# 22-RGMII_ETHERNET_PHY_-_MCU.net
KiCad netlist of a schematic drawn in Altium Designer
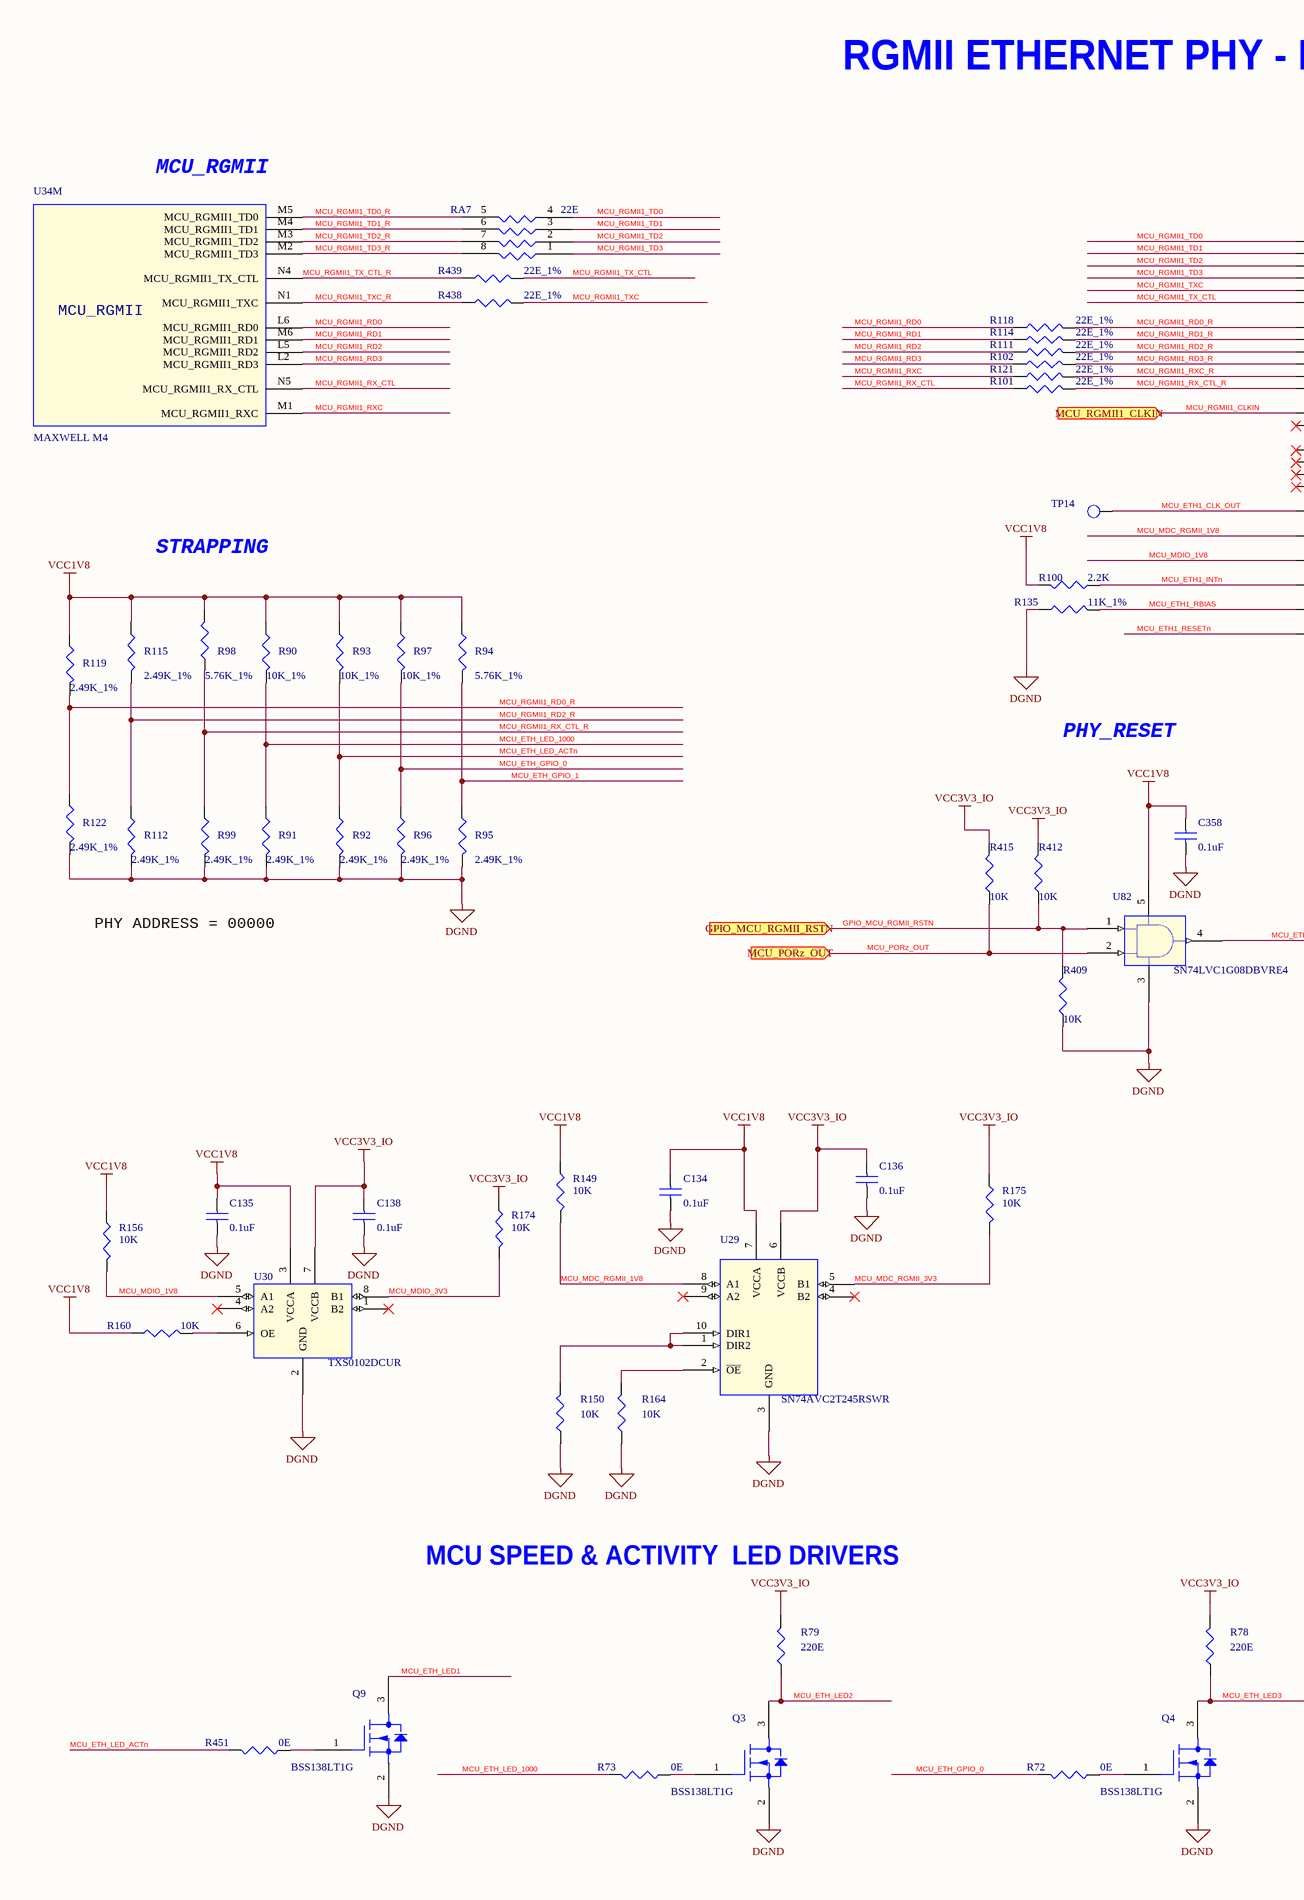
[diagram p0: 22-RGMII ETHERNET PHY - MCU.SchDoc, left]
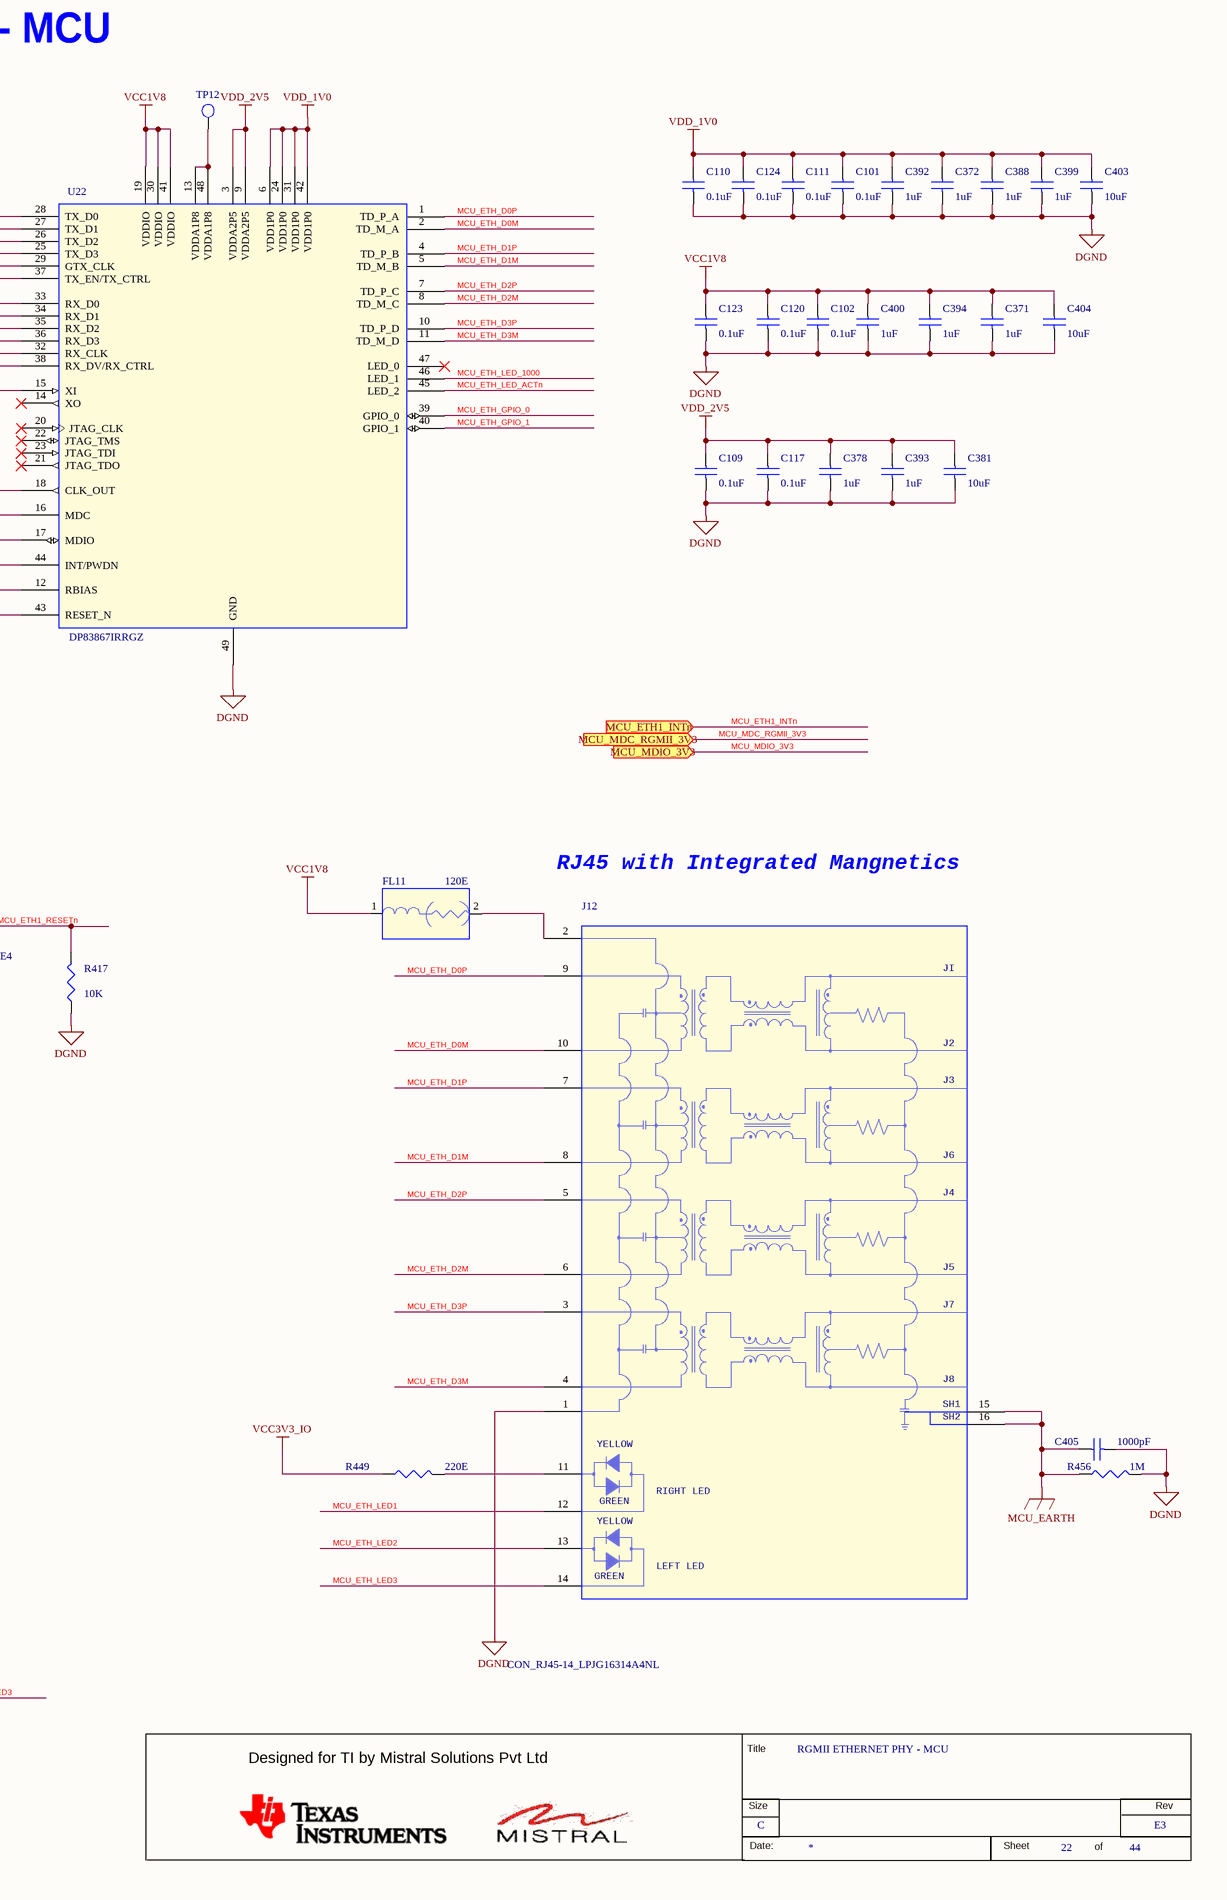
[diagram p1: 22-RGMII ETHERNET PHY - MCU.SchDoc, right]

(export (version "E")
  (design (tool "Eeschema 10.0.6"))
  (components
    (comp (ref "C101")
      (value "0.1uF")
      (footprint "CAP0201_0-5")
      (description "CAP CERAMIC 0.1uF 16V 10% X5R 0201")
      (fields
        (field (name "MISTRAL PART NO") "120009030072-R")
        (field (name "MFR_PART_NUMBER") "GRM033R61C104KE84J")
      )
      (libsource (lib "*") (part "CAP_Dup5"))
    )
    (comp (ref "C102")
      (value "0.1uF")
      (footprint "CAP0201_0-5")
      (description "CAP CERAMIC 0.1uF 16V 10% X5R 0201")
      (fields
        (field (name "MISTRAL PART NO") "120009030072-R")
        (field (name "MFR_PART_NUMBER") "GRM033R61C104KE84J")
      )
      (libsource (lib "*") (part "CAP_Dup5"))
    )
    (comp (ref "C109")
      (value "0.1uF")
      (footprint "CAP0201_0-5")
      (description "CAP CERAMIC 0.1uF 16V 10% X5R 0201")
      (fields (field (name "DISTRIBUTOR_PART_NUMBER") "490-16742-1-ND") (field (name "VOLTAGE") "16V"))
      (libsource (lib "*") (part "CAP_Dup5"))
    )
    (comp (ref "C110")
      (value "0.1uF")
      (footprint "CAP0201_0-5")
      (description "CAP CERAMIC 0.1uF 16V 10% X5R 0201")
      (fields (field (name "DISTRIBUTOR_PART_NUMBER") "490-16742-1-ND") (field (name "VOLTAGE") "16V"))
      (libsource (lib "*") (part "CAP_Dup5"))
    )
    (comp (ref "C111")
      (value "0.1uF")
      (footprint "CAP0201_0-5")
      (description "CAP CERAMIC 0.1uF 16V 10% X5R 0201")
      (fields
        (field (name "MISTRAL PART NO") "120009030072-R")
        (field (name "MFR_PART_NUMBER") "GRM033R61C104KE84J")
      )
      (libsource (lib "*") (part "CAP_Dup5"))
    )
    (comp (ref "C117")
      (value "0.1uF")
      (footprint "CAP0201_0-5")
      (description "CAP CERAMIC 0.1uF 16V 10% X5R 0201")
      (fields
        (field (name "MISTRAL PART NO") "120009030072-R")
        (field (name "MFR_PART_NUMBER") "GRM033R61C104KE84J")
      )
      (libsource (lib "*") (part "CAP_Dup5"))
    )
    (comp (ref "C120")
      (value "0.1uF")
      (footprint "CAP0201_0-5")
      (description "CAP CERAMIC 0.1uF 16V 10% X5R 0201")
      (fields
        (field (name "MISTRAL PART NO") "120009030072-R")
        (field (name "MFR_PART_NUMBER") "GRM033R61C104KE84J")
      )
      (libsource (lib "*") (part "CAP_Dup5"))
    )
    (comp (ref "C123")
      (value "0.1uF")
      (footprint "CAP0201_0-5")
      (description "CAP CERAMIC 0.1uF 16V 10% X5R 0201")
      (fields
        (field (name "MISTRAL PART NO") "120009030072-R")
        (field (name "MFR_PART_NUMBER") "GRM033R61C104KE84J")
      )
      (libsource (lib "*") (part "CAP_Dup5"))
    )
    (comp (ref "C124")
      (value "0.1uF")
      (footprint "CAP0201_0-5")
      (description "CAP CERAMIC 0.1uF 16V 10% X5R 0201")
      (fields (field (name "DISTRIBUTOR_PART_NUMBER") "490-16742-1-ND") (field (name "VOLTAGE") "16V"))
      (libsource (lib "*") (part "CAP_Dup5"))
    )
    (comp (ref "C134")
      (value "0.1uF")
      (footprint "CAP0201_0-5")
      (description "CAP CERAMIC 0.1uF 16V 10% X5R 0201")
      (fields (field (name "DISTRIBUTOR_PART_NUMBER") "490-16742-1-ND") (field (name "VOLTAGE") "16V"))
      (libsource (lib "*") (part "CAP_Dup5"))
    )
    (comp (ref "C135")
      (value "0.1uF")
      (footprint "CAP0201_0-5")
      (description "CAP CERAMIC 0.1uF 16V 10% X5R 0201")
      (fields (field (name "DISTRIBUTOR_PART_NUMBER") "490-16742-1-ND") (field (name "VOLTAGE") "16V"))
      (libsource (lib "*") (part "CAP_Dup5"))
    )
    (comp (ref "C136")
      (value "0.1uF")
      (footprint "CAP0201_0-5")
      (description "CAP CERAMIC 0.1uF 16V 10% X5R 0201")
      (fields (field (name "DISTRIBUTOR_PART_NUMBER") "490-16742-1-ND") (field (name "VOLTAGE") "16V"))
      (libsource (lib "*") (part "CAP_Dup5"))
    )
    (comp (ref "C138")
      (value "0.1uF")
      (footprint "CAP0201_0-5")
      (description "CAP CERAMIC 0.1uF 16V 10% X5R 0201")
      (fields (field (name "DISTRIBUTOR_PART_NUMBER") "490-16742-1-ND") (field (name "VOLTAGE") "16V"))
      (libsource (lib "*") (part "CAP_Dup5"))
    )
    (comp (ref "C358")
      (value "0.1uF")
      (footprint "CAP0201_0-5")
      (description "CAP CERAMIC 0.1uF 16V 10% X5R 0201")
      (fields (field (name "DISTRIBUTOR_PART_NUMBER") "490-16742-1-ND") (field (name "VOLTAGE") "16V"))
      (libsource (lib "*") (part "CAP_Dup5"))
    )
    (comp (ref "C371")
      (value "1uF")
      (footprint "CAP0402_0-75")
      (description "CAP CERAMIC 1uF 16V 20% X5R 0402")
      (fields
        (field (name "MISTRAL PART NO") "120018020006-R")
        (field (name "MFR_PART_NUMBER") "EMK105BJ105MV-F")
      )
      (libsource (lib "*") (part "CAP_Dup5"))
    )
    (comp (ref "C372")
      (value "1uF")
      (footprint "CAP0402_0-75")
      (description "CAP CERAMIC 1uF 16V 20% X5R 0402")
      (fields
        (field (name "MISTRAL PART NO") "120018020006-R")
        (field (name "MFR_PART_NUMBER") "EMK105BJ105MV-F")
      )
      (libsource (lib "*") (part "CAP_Dup5"))
    )
    (comp (ref "C378")
      (value "1uF")
      (footprint "CAP0402_0-75")
      (description "CAP CERAMIC 1uF 16V 20% X5R 0402")
      (fields (field (name "DISTRIBUTOR_PART_NUMBER") "587-5514-1-ND") (field (name "VOLTAGE") "16V"))
      (libsource (lib "*") (part "CAP_Dup5"))
    )
    (comp (ref "C381")
      (value "10uF")
      (footprint "CAP0603_1")
      (description "CAP CERAMIC 10uF 10V 10% X5R 0603")
      (fields (field (name "DISTRIBUTOR_PART_NUMBER") "478-10766-1-ND") (field (name "VOLTAGE") "10V"))
      (libsource (lib "*") (part "CAP_Dup5"))
    )
    (comp (ref "C388")
      (value "1uF")
      (footprint "CAP0402_0-75")
      (description "CAP CERAMIC 1uF 16V 20% X5R 0402")
      (fields (field (name "DISTRIBUTOR_PART_NUMBER") "587-5514-1-ND") (field (name "VOLTAGE") "16V"))
      (libsource (lib "*") (part "CAP_Dup5"))
    )
    (comp (ref "C392")
      (value "1uF")
      (footprint "CAP0402_0-75")
      (description "CAP CERAMIC 1uF 16V 20% X5R 0402")
      (fields (field (name "DISTRIBUTOR_PART_NUMBER") "587-5514-1-ND") (field (name "VOLTAGE") "16V"))
      (libsource (lib "*") (part "CAP_Dup5"))
    )
    (comp (ref "C393")
      (value "1uF")
      (footprint "CAP0402_0-75")
      (description "CAP CERAMIC 1uF 16V 20% X5R 0402")
      (fields (field (name "DISTRIBUTOR_PART_NUMBER") "587-5514-1-ND") (field (name "VOLTAGE") "16V"))
      (libsource (lib "*") (part "CAP_Dup5"))
    )
    (comp (ref "C394")
      (value "1uF")
      (footprint "CAP0402_0-75")
      (description "CAP CERAMIC 1uF 16V 20% X5R 0402")
      (fields
        (field (name "MISTRAL PART NO") "120018020006-R")
        (field (name "MFR_PART_NUMBER") "EMK105BJ105MV-F")
      )
      (libsource (lib "*") (part "CAP_Dup5"))
    )
    (comp (ref "C399")
      (value "1uF")
      (footprint "CAP0402_0-75")
      (description "CAP CERAMIC 1uF 16V 20% X5R 0402")
      (fields
        (field (name "MISTRAL PART NO") "120018020006-R")
        (field (name "MFR_PART_NUMBER") "EMK105BJ105MV-F")
      )
      (libsource (lib "*") (part "CAP_Dup5"))
    )
    (comp (ref "C400")
      (value "1uF")
      (footprint "CAP0402_0-75")
      (description "CAP CERAMIC 1uF 16V 20% X5R 0402")
      (fields
        (field (name "MISTRAL PART NO") "120018020006-R")
        (field (name "MFR_PART_NUMBER") "EMK105BJ105MV-F")
      )
      (libsource (lib "*") (part "CAP_Dup5"))
    )
    (comp (ref "C403")
      (value "10uF")
      (footprint "CAP0603_1")
      (description "CAP CERAMIC 10uF 10V 10% X5R 0603")
      (fields (field (name "DISTRIBUTOR_PART_NUMBER") "478-10766-1-ND") (field (name "VOLTAGE") "10V"))
      (libsource (lib "*") (part "CAP_Dup5"))
    )
    (comp (ref "C404")
      (value "10uF")
      (footprint "CAP0603_1")
      (description "CAP CERAMIC 10uF 10V 10% X5R 0603")
      (fields
        (field (name "MISTRAL PART NO") "120010080001-R")
        (field (name "MFR_PART_NUMBER") "0603ZD106KAT2A")
      )
      (libsource (lib "*") (part "CAP_Dup5"))
    )
    (comp (ref "C405")
      (value "1000pF")
      (footprint "CAP1206")
      (description "CAP CERAMIC 1000pF 2KV 10% X7R 1206")
      (fields
        (field (name "MISTRAL PART NO") "120009030147-R")
        (field (name "MFR_PART_NUMBER") "1206GC102KAT1A")
      )
      (libsource (lib "*") (part "CAP_Dup5"))
    )
    (comp (ref "FL11")
      (value "120E")
      (footprint "EMIFIL_BLM15A_0402_0-6")
      (description "FERRITE CHIP 120E 1.3A 0402")
      (fields
        (field (name "MISTRAL PART NO") "130012030043-R")
        (field (name "MFR_PART_NUMBER") "BLM15PD121SN1")
      )
      (libsource (lib "*") (part "EMIFILTER_IND"))
    )
    (comp (ref "J12")
      (value "CON_RJ45-14_LPJG16314A4NL")
      (footprint "CON_RJ45-14_LPJG16314A4NL_S_R_T_13-6")
      (description "CON RJ-45 FEMALE 14POS RT TH")
      (fields (field (name "DISTRIBUTOR_PART_NUMBER") "NA") (field (name "MFR_PART_NUMBER") "LPJG16314A4NL"))
      (libsource (lib "*") (part "CON_RJ45-14_LPJG16314A4NL"))
    )
    (comp (ref "Q3")
      (value "BSS138LT1G")
      (footprint "SOT23-123")
      (description "IC MOSFET N-CHANNEL 50V, SOT23-3")
      (fields (field (name "MISTRAL PART NO") "142016040001-R") (field (name "TOLERANCE") "NA"))
      (libsource (lib "*") (part "MOSFET_BSS138LT1G"))
    )
    (comp (ref "Q4")
      (value "BSS138LT1G")
      (footprint "SOT23-123")
      (description "IC MOSFET N-CHANNEL 50V, SOT23-3")
      (fields (field (name "MISTRAL PART NO") "142016040001-R") (field (name "TOLERANCE") "NA"))
      (libsource (lib "*") (part "MOSFET_BSS138LT1G"))
    )
    (comp (ref "Q9")
      (value "BSS138LT1G")
      (footprint "SOT23-123")
      (description "IC MOSFET N-CHANNEL 50V, SOT23-3")
      (fields (field (name "MISTRAL PART NO") "142016040001-R") (field (name "TOLERANCE") "NA"))
      (libsource (lib "*") (part "MOSFET_BSS138LT1G"))
    )
    (comp (ref "R72")
      (value "0E")
      (footprint "RES0402_0-5")
      (description "RES 0E 1/16W 0402")
      (fields
        (field (name "MISTRAL PART NO") "110010080019-P")
        (field (name "MFR_PART_NUMBER") "CRCW04020000Z0ED")
      )
      (libsource (lib "*") (part "RESISTOR_Dup4"))
    )
    (comp (ref "R73")
      (value "0E")
      (footprint "RES0402_0-5")
      (description "RES 0E 1/16W 0402")
      (fields
        (field (name "MISTRAL PART NO") "110010080019-P")
        (field (name "MFR_PART_NUMBER") "CRCW04020000Z0ED")
      )
      (libsource (lib "*") (part "RESISTOR_Dup4"))
    )
    (comp (ref "R78")
      (value "220E")
      (footprint "RES0402_0-5")
      (description "RES 220E 1/16W 5% 0402")
      (fields
        (field (name "MISTRAL PART NO") "110009030506-R")
        (field (name "MFR_PART_NUMBER") "ERJ-2GEJ221X")
      )
      (libsource (lib "*") (part "RESISTOR_Dup5"))
    )
    (comp (ref "R79")
      (value "220E")
      (footprint "RES0402_0-5")
      (description "RES 220E 1/16W 5% 0402")
      (fields
        (field (name "MISTRAL PART NO") "110009030506-R")
        (field (name "MFR_PART_NUMBER") "ERJ-2GEJ221X")
      )
      (libsource (lib "*") (part "RESISTOR_Dup5"))
    )
    (comp (ref "R90")
      (value "10K_1%")
      (footprint "RES0402_0-5")
      (description "RES 10K 1/16W 1% 0402")
      (fields (field (name "DISTRIBUTOR_PART_NUMBER") "311-10.0KLRTR-ND") (field (name "VOLTAGE") "NA"))
      (libsource (lib "*") (part "RESISTOR_Dup5"))
    )
    (comp (ref "R91")
      (value "2.49K_1%")
      (footprint "RES0402")
      (description "RES 2.49K 1/16W 1% 0402")
      (fields
        (field (name "MISTRAL PART NO") "110016050020-R")
        (field (name "MFR_PART_NUMBER") "RC0402FR-072K49L")
      )
      (libsource (lib "*") (part "RESISTOR_Dup5"))
    )
    (comp (ref "R92")
      (value "2.49K_1%")
      (footprint "RES0402")
      (description "RES 2.49K 1/16W 1% 0402")
      (fields
        (field (name "MISTRAL PART NO") "110016050020-R")
        (field (name "MFR_PART_NUMBER") "RC0402FR-072K49L")
      )
      (libsource (lib "*") (part "RESISTOR_Dup5"))
    )
    (comp (ref "R93")
      (value "10K_1%")
      (footprint "RES0402_0-5")
      (description "RES 10K 1/16W 1% 0402")
      (fields (field (name "DISTRIBUTOR_PART_NUMBER") "311-10.0KLRTR-ND") (field (name "VOLTAGE") "NA"))
      (libsource (lib "*") (part "RESISTOR_Dup5"))
    )
    (comp (ref "R94")
      (value "5.76K_1%")
      (footprint "RES0402")
      (description "RES 5.76K 1/10W 1% 0402")
      (fields
        (field (name "MISTRAL PART NO") "110009030945-R")
        (field (name "MFR_PART_NUMBER") "ERJ-2RKF5761X")
      )
      (libsource (lib "*") (part "RESISTOR_Dup5"))
    )
    (comp (ref "R95")
      (value "2.49K_1%")
      (footprint "RES0402")
      (description "RES 2.49K 1/16W 1% 0402")
      (fields
        (field (name "MISTRAL PART NO") "110016050020-R")
        (field (name "MFR_PART_NUMBER") "RC0402FR-072K49L")
      )
      (libsource (lib "*") (part "RESISTOR_Dup5"))
    )
    (comp (ref "R96")
      (value "2.49K_1%")
      (footprint "RES0402")
      (description "RES 2.49K 1/16W 1% 0402")
      (fields
        (field (name "MISTRAL PART NO") "110016050020-R")
        (field (name "MFR_PART_NUMBER") "RC0402FR-072K49L")
      )
      (libsource (lib "*") (part "RESISTOR_Dup5"))
    )
    (comp (ref "R97")
      (value "10K_1%")
      (footprint "RES0402_0-5")
      (description "RES 10K 1/16W 1% 0402")
      (fields
        (field (name "MISTRAL PART NO") "110009030220-P")
        (field (name "MFR_PART_NUMBER") "RC0402FR-0710KL")
      )
      (libsource (lib "*") (part "RESISTOR_Dup5"))
    )
    (comp (ref "R98")
      (value "5.76K_1%")
      (footprint "RES0402")
      (description "RES 5.76K 1/10W 1% 0402")
      (fields (field (name "DISTRIBUTOR_PART_NUMBER") "P5.76KLCT-ND") (field (name "TOLERANCE") "1%"))
      (libsource (lib "*") (part "RESISTOR_Dup5"))
    )
    (comp (ref "R99")
      (value "2.49K_1%")
      (footprint "RES0402")
      (description "RES 2.49K 1/16W 1% 0402")
      (fields
        (field (name "MISTRAL PART NO") "110016050020-R")
        (field (name "MFR_PART_NUMBER") "RC0402FR-072K49L")
      )
      (libsource (lib "*") (part "RESISTOR_Dup5"))
    )
    (comp (ref "R100")
      (value "2.2K")
      (footprint "RES0402_0-5")
      (description "RES 2.2K 1/16W 5% 0402")
      (fields (field (name "DISTRIBUTOR_PART_NUMBER") "311-2.2KJRCT-ND") (field (name "VOLTAGE") "NA"))
      (libsource (lib "*") (part "RESISTOR_Dup5"))
    )
    (comp (ref "R101")
      (value "22E_1%")
      (footprint "RES0402")
      (description "RES 22E 1/16W 1% 0402")
      (fields
        (field (name "CUST_PART_NUMBER") "4700-80047E")
        (field (name "DISTRIBUTOR_PART_NUMBER") "311-22.0LRCT-ND")
      )
      (libsource (lib "*") (part "RESISTOR_Dup5"))
    )
    (comp (ref "R102")
      (value "22E_1%")
      (footprint "RES0402")
      (description "RES 22E 1/16W 1% 0402")
      (fields
        (field (name "MISTRAL PART NO") "110009090004-P")
        (field (name "MFR_PART_NUMBER") "RC0402FR-0722RL")
      )
      (libsource (lib "*") (part "RESISTOR_Dup5"))
    )
    (comp (ref "R111")
      (value "22E_1%")
      (footprint "RES0402")
      (description "RES 22E 1/16W 1% 0402")
      (fields
        (field (name "CUST_PART_NUMBER") "4700-80047E")
        (field (name "DISTRIBUTOR_PART_NUMBER") "311-22.0LRCT-ND")
      )
      (libsource (lib "*") (part "RESISTOR_Dup5"))
    )
    (comp (ref "R112")
      (value "2.49K_1%")
      (footprint "RES0402")
      (description "RES 2.49K 1/16W 1% 0402")
      (fields
        (field (name "MISTRAL PART NO") "110016050020-R")
        (field (name "MFR_PART_NUMBER") "RC0402FR-072K49L")
      )
      (libsource (lib "*") (part "RESISTOR_Dup5"))
    )
    (comp (ref "R114")
      (value "22E_1%")
      (footprint "RES0402")
      (description "RES 22E 1/16W 1% 0402")
      (fields
        (field (name "MISTRAL PART NO") "110009090004-P")
        (field (name "MFR_PART_NUMBER") "RC0402FR-0722RL")
      )
      (libsource (lib "*") (part "RESISTOR_Dup5"))
    )
    (comp (ref "R115")
      (value "2.49K_1%")
      (footprint "RES0402")
      (description "RES 2.49K 1/16W 1% 0402")
      (fields
        (field (name "MISTRAL PART NO") "110016050020-R")
        (field (name "MFR_PART_NUMBER") "RC0402FR-072K49L")
      )
      (libsource (lib "*") (part "RESISTOR_Dup5"))
    )
    (comp (ref "R118")
      (value "22E_1%")
      (footprint "RES0402")
      (description "RES 22E 1/16W 1% 0402")
      (fields
        (field (name "CUST_PART_NUMBER") "4700-80047E")
        (field (name "DISTRIBUTOR_PART_NUMBER") "311-22.0LRCT-ND")
      )
      (libsource (lib "*") (part "RESISTOR_Dup5"))
    )
    (comp (ref "R119")
      (value "2.49K_1%")
      (footprint "RES0402")
      (description "RES 2.49K 1/16W 1% 0402")
      (fields (field (name "DISTRIBUTOR_PART_NUMBER") "311-2.49KLRCT-ND") (field (name "VOLTAGE") "NA"))
      (libsource (lib "*") (part "RESISTOR_Dup5"))
    )
    (comp (ref "R121")
      (value "22E_1%")
      (footprint "RES0402")
      (description "RES 22E 1/16W 1% 0402")
      (fields
        (field (name "MISTRAL PART NO") "110009090004-P")
        (field (name "MFR_PART_NUMBER") "RC0402FR-0722RL")
      )
      (libsource (lib "*") (part "RESISTOR_Dup5"))
    )
    (comp (ref "R122")
      (value "2.49K_1%")
      (footprint "RES0402")
      (description "RES 2.49K 1/16W 1% 0402")
      (fields
        (field (name "MISTRAL PART NO") "110016050020-R")
        (field (name "MFR_PART_NUMBER") "RC0402FR-072K49L")
      )
      (libsource (lib "*") (part "RESISTOR_Dup5"))
    )
    (comp (ref "R135")
      (value "11K_1%")
      (footprint "RES0402_0-5")
      (description "RES 11K 1/16W 1% 0402")
      (fields
        (field (name "MISTRAL PART NO") "110015110012-P")
        (field (name "MFR_PART_NUMBER") "RC0402FR-0711KL")
      )
      (libsource (lib "*") (part "RESISTOR_Dup5"))
    )
    (comp (ref "R149")
      (value "10K")
      (footprint "RES0201")
      (description "RES 10K 1/20W 5% 0201")
      (fields
        (field (name "MISTRAL PART NO") "110010070051-R")
        (field (name "MFR_PART_NUMBER") "NRC02J103TRF")
      )
      (libsource (lib "*") (part "RESISTOR_Dup5"))
    )
    (comp (ref "R150")
      (value "10K")
      (footprint "RES0402_0-5")
      (description "RES 10K 1/16W 5% 0402")
      (fields (field (name "DISTRIBUTOR_PART_NUMBER") "311-10KJRCT-ND") (field (name "VOLTAGE") "NA"))
      (libsource (lib "*") (part "RESISTOR_Dup5"))
    )
    (comp (ref "R156")
      (value "10K")
      (footprint "RES0201")
      (description "RES 10K 1/20W 5% 0201")
      (fields (field (name "DISTRIBUTOR_PART_NUMBER") "NA") (field (name "VOLTAGE") "50V"))
      (libsource (lib "*") (part "RESISTOR_Dup5"))
    )
    (comp (ref "R160")
      (value "10K")
      (footprint "RES0402_0-5")
      (description "RES 10K 1/16W 5% 0402")
      (fields
        (field (name "MISTRAL PART NO") "110009030208-R")
        (field (name "MFR_PART_NUMBER") "RC0402JR-0710KL")
      )
      (libsource (lib "*") (part "RESISTOR_Dup5"))
    )
    (comp (ref "R164")
      (value "10K")
      (footprint "RES0402_0-5")
      (description "RES 10K 1/16W 5% 0402")
      (fields (field (name "DISTRIBUTOR_PART_NUMBER") "311-10KJRCT-ND") (field (name "VOLTAGE") "NA"))
      (libsource (lib "*") (part "RESISTOR_Dup5"))
    )
    (comp (ref "R174")
      (value "10K")
      (footprint "RES0201")
      (description "RES 10K 1/20W 5% 0201")
      (fields (field (name "DISTRIBUTOR_PART_NUMBER") "NA") (field (name "VOLTAGE") "50V"))
      (libsource (lib "*") (part "RESISTOR_Dup5"))
    )
    (comp (ref "R175")
      (value "10K")
      (footprint "RES0201")
      (description "RES 10K 1/20W 5% 0201")
      (fields
        (field (name "MISTRAL PART NO") "110010070051-R")
        (field (name "MFR_PART_NUMBER") "NRC02J103TRF")
      )
      (libsource (lib "*") (part "RESISTOR_Dup5"))
    )
    (comp (ref "R409")
      (value "10K")
      (footprint "RES0402_0-5")
      (description "RES 10K 1/16W 5% 0402")
      (fields (field (name "DISTRIBUTOR_PART_NUMBER") "311-10KJRCT-ND") (field (name "VOLTAGE") "NA"))
      (libsource (lib "*") (part "RESISTOR_Dup5"))
    )
    (comp (ref "R412")
      (value "10K")
      (footprint "RES0402_0-5")
      (description "RES 10K 1/16W 5% 0402")
      (fields
        (field (name "MISTRAL PART NO") "110009030208-R")
        (field (name "MFR_PART_NUMBER") "RC0402JR-0710KL")
      )
      (libsource (lib "*") (part "RESISTOR_Dup5"))
    )
    (comp (ref "R415")
      (value "10K")
      (footprint "RES0402_0-5")
      (description "RES 10K 1/16W 5% 0402")
      (fields (field (name "DISTRIBUTOR_PART_NUMBER") "311-10KJRCT-ND") (field (name "VOLTAGE") "NA"))
      (libsource (lib "*") (part "RESISTOR_Dup5"))
    )
    (comp (ref "R417")
      (value "10K")
      (footprint "RES0402_0-5")
      (description "RES 10K 1/16W 5% 0402")
      (fields
        (field (name "MISTRAL PART NO") "110009030208-R")
        (field (name "MFR_PART_NUMBER") "RC0402JR-0710KL")
      )
      (libsource (lib "*") (part "RESISTOR_Dup5"))
    )
    (comp (ref "R438")
      (value "22E_1%")
      (footprint "RES0402")
      (description "RES 22E 1/16W 1% 0402")
      (fields
        (field (name "CUST_PART_NUMBER") "4700-80047E")
        (field (name "DISTRIBUTOR_PART_NUMBER") "311-22.0LRCT-ND")
      )
      (libsource (lib "*") (part "RESISTOR_Dup5"))
    )
    (comp (ref "R439")
      (value "22E_1%")
      (footprint "RES0402")
      (description "RES 22E 1/16W 1% 0402")
      (fields
        (field (name "MISTRAL PART NO") "110009090004-P")
        (field (name "MFR_PART_NUMBER") "RC0402FR-0722RL")
      )
      (libsource (lib "*") (part "RESISTOR_Dup5"))
    )
    (comp (ref "R449")
      (value "220E")
      (footprint "RES0402_0-5")
      (description "RES 220E 1/16W 5% 0402")
      (fields (field (name "DISTRIBUTOR_PART_NUMBER") "P220JCT-ND") (field (name "TOLERANCE") "5%"))
      (libsource (lib "*") (part "RESISTOR_Dup5"))
    )
    (comp (ref "R451")
      (value "0E")
      (footprint "RES0402_0-5")
      (description "RES 0E 1/16W 0402")
      (fields
        (field (name "MISTRAL PART NO") "110010080019-P")
        (field (name "MFR_PART_NUMBER") "CRCW04020000Z0ED")
      )
      (libsource (lib "*") (part "RESISTOR_Dup4"))
    )
    (comp (ref "R456")
      (value "1M")
      (footprint "RES0603_0-75")
      (description "RES 1M 1/10W 5% 0603")
      (fields (field (name "DISTRIBUTOR_PART_NUMBER") "P1.0MGCT-ND") (field (name "VOLTAGE") "NA"))
      (libsource (lib "*") (part "RESISTOR_Dup5"))
    )
    (comp (ref "RA7")
      (value "22E")
      (footprint "RESA_EXB28V_0402-4_0-5")
      (description "RES ARRAY 22E 31mW 5% 0402")
      (fields
        (field (name "MISTRAL PART NO") "110009030021-R")
        (field (name "MFR_PART_NUMBER") "EXB-28V220JX")
      )
      (libsource (lib "*") (part "RESARR_ISO4"))
    )
    (comp (ref "TP12")
      (value "TP40_SMD")
      (footprint "TP40_SMD")
      (description "TESTPOINT CIR 40 SMD")
      (fields (field (name "MISTRAL PART NO") "130009030933") (field (name "DISTRIBUTOR_PART_NUMBER") "NA"))
      (libsource (lib "*") (part "TESTPOINT"))
    )
    (comp (ref "TP14")
      (value "TP40_SMD")
      (footprint "TP40_SMD")
      (description "TESTPOINT CIR 40 SMD")
      (fields (field (name "VOLTAGE") "NA") (field (name "MISTRAL PART NO") "130009030933"))
      (libsource (lib "*") (part "TESTPOINT"))
    )
    (comp (ref "U22")
      (value "DP83867IRRGZ")
      (footprint "QFN48_19-68_280X280_1")
      (description "IC HIGH IMMUNITY 10/100/1000 Mb/s ETHERNET PHY LAYER TRANSCEIVER VQFN48")
      (fields (field (name "DISTRIBUTOR_PART_NUMBER") "DP83867IRRGZT-ND") (field (name "VOLTAGE") "NA"))
      (libsource (lib "*") (part "DP83867IRRGZ_VQFN48"))
    )
    (comp (ref "U29")
      (value "SN74AVC2T245RSWR")
      (footprint "QFN10_15-74_75X60")
      (description "IC DUAL-BIT DUAL SUPPLY BUS TRANSCEIVER QFN10")
      (fields
        (field (name "MISTRAL PART NO") "143009030061-R")
        (field (name "DISTRIBUTOR_PART_NUMBER") "296-23684-1-ND")
      )
      (libsource (lib "*") (part "SN74AVC2T245RSWR_QFN10"))
    )
    (comp (ref "U30")
      (value "TXS0102DCUR")
      (footprint "VSSOP8_19-68_85X95_0-9")
      (description "IC 2BIT BI-DIR VOLTAGE-LEVEL TRANSLATOR US8(VSSOP8)")
      (fields
        (field (name "DISTRIBUTOR_PART_NUMBER") "296-21931-1-ND")
        (field (name "VOLTAGE") "NA")
        (field (name "LIBRARY PATH") "Y~{:}MIS_DATABAS~{E}Librar~{y}ALTIUM_TOO~{L}SCHEMATICS_PART~{S}MS_MISCINTERFACE_Library.schlib")
      )
      (libsource (lib "*") (part "TXS0102DCUR_VSSOP8"))
    )
    (comp (ref "U34")
      (value "MAXWELL M4")
      (footprint "BGA784_31-49_910X910_1-7")
      (description "IC MAXWELL MICRO CONTROLLER UNIT BGA784")
      (fields
        (field (name "MISTRAL PART NO") "141217100003")
        (field (name "MFR_PART_NUMBER") "MAXWELL M4_EVM")
      )
      (libsource (lib "*") (part "AM654X_BGA784"))
    )
    (comp (ref "U82")
      (value "SN74LVC1G08DBVRE4")
      (footprint "SOT23-5")
      (description "IC SINGLE 2-INPUT POSITIVE AND GATE SOT23-5")
      (fields
        (field (name "DISTRIBUTOR_PART_NUMBER") "SN74LVC1G08DBVRE4-ND")
        (field (name "MISTRAL PART NO") "141009060026-R")
      )
      (libsource (lib "*") (part "SN74LVC1G08DBVRE4_SOT23-5"))
    )
  )
  (nets
    (net (code "1") (name "/GPIO_MCU_RGMII_RSTN") (class "Default")
      (node (ref "R409") (pin "2") (pinfunction "2_2") (pintype "passive"))
      (node (ref "R412") (pin "1") (pinfunction "1_1") (pintype "passive"))
      (node (ref "U82") (pin "1") (pinfunction "A_1") (pintype "input"))
    )
    (net (code "2") (name "/MCU_ETH1_CLK_OUT") (class "Default")
      (node (ref "TP14") (pin "1") (pinfunction "TP_1") (pintype "passive"))
      (node (ref "U22") (pin "18") (pinfunction "CLK_OUT_18") (pintype "output"))
    )
    (net (code "3") (name "/MCU_ETH1_INTn") (class "Default")
      (node (ref "R100") (pin "1") (pinfunction "1_1") (pintype "passive"))
      (node (ref "U22") (pin "44") (pinfunction "INT/PWDN_44") (pintype "passive"))
    )
    (net (code "4") (name "/MCU_ETH1_RBIAS") (class "Default")
      (node (ref "R135") (pin "1") (pinfunction "1_1") (pintype "passive"))
      (node (ref "U22") (pin "12") (pinfunction "RBIAS_12") (pintype "passive"))
    )
    (net (code "5") (name "/MCU_ETH1_RESETn") (class "Default")
      (node (ref "R417") (pin "1") (pinfunction "1_1") (pintype "passive"))
      (node (ref "U22") (pin "43") (pinfunction "RESET_N_43") (pintype "passive"))
      (node (ref "U82") (pin "4") (pinfunction "Y_4") (pintype "output"))
    )
    (net (code "6") (name "/MCU_ETH_D0M") (class "Default")
      (node (ref "J12") (pin "10") (pinfunction "MX0-_10") (pintype "passive"))
      (node (ref "U22") (pin "2") (pinfunction "TD_M_A_2") (pintype "passive"))
    )
    (net (code "7") (name "/MCU_ETH_D0P") (class "Default")
      (node (ref "J12") (pin "9") (pinfunction "MX0+_9") (pintype "passive"))
      (node (ref "U22") (pin "1") (pinfunction "TD_P_A_1") (pintype "passive"))
    )
    (net (code "8") (name "/MCU_ETH_D1M") (class "Default")
      (node (ref "J12") (pin "8") (pinfunction "MX1-_8") (pintype "passive"))
      (node (ref "U22") (pin "5") (pinfunction "TD_M_B_5") (pintype "passive"))
    )
    (net (code "9") (name "/MCU_ETH_D1P") (class "Default")
      (node (ref "J12") (pin "7") (pinfunction "MX1+_7") (pintype "passive"))
      (node (ref "U22") (pin "4") (pinfunction "TD_P_B_4") (pintype "passive"))
    )
    (net (code "10") (name "/MCU_ETH_D2M") (class "Default")
      (node (ref "J12") (pin "6") (pinfunction "MX2-_6") (pintype "passive"))
      (node (ref "U22") (pin "8") (pinfunction "TD_M_C_8") (pintype "passive"))
    )
    (net (code "11") (name "/MCU_ETH_D2P") (class "Default")
      (node (ref "J12") (pin "5") (pinfunction "MX2+_5") (pintype "passive"))
      (node (ref "U22") (pin "7") (pinfunction "TD_P_C_7") (pintype "passive"))
    )
    (net (code "12") (name "/MCU_ETH_D3M") (class "Default")
      (node (ref "J12") (pin "4") (pinfunction "MX3-_4") (pintype "passive"))
      (node (ref "U22") (pin "11") (pinfunction "TD_M_D_11") (pintype "passive"))
    )
    (net (code "13") (name "/MCU_ETH_D3P") (class "Default")
      (node (ref "J12") (pin "3") (pinfunction "MX3+_3") (pintype "passive"))
      (node (ref "U22") (pin "10") (pinfunction "TD_P_D_10") (pintype "passive"))
    )
    (net (code "14") (name "/MCU_ETH_GPIO_0") (class "Default")
      (node (ref "R72") (pin "2") (pinfunction "2_2") (pintype "passive"))
      (node (ref "R96") (pin "1") (pinfunction "1_1") (pintype "passive"))
      (node (ref "R97") (pin "2") (pinfunction "2_2") (pintype "passive"))
      (node (ref "U22") (pin "39") (pinfunction "GPIO_0_39") (pintype "bidirectional"))
    )
    (net (code "15") (name "/MCU_ETH_GPIO_1") (class "Default")
      (node (ref "R94") (pin "2") (pinfunction "2_2") (pintype "passive"))
      (node (ref "R95") (pin "1") (pinfunction "1_1") (pintype "passive"))
      (node (ref "U22") (pin "40") (pinfunction "GPIO_1_40") (pintype "bidirectional"))
    )
    (net (code "16") (name "/MCU_ETH_LED1") (class "Default")
      (node (ref "J12") (pin "12") (pinfunction "12_12") (pintype "passive"))
      (node (ref "Q9") (pin "3") (pinfunction "D_3") (pintype "passive"))
    )
    (net (code "17") (name "/MCU_ETH_LED2") (class "Default")
      (node (ref "J12") (pin "13") (pinfunction "13_13") (pintype "passive"))
      (node (ref "Q3") (pin "3") (pinfunction "D_3") (pintype "passive"))
      (node (ref "R79") (pin "1") (pinfunction "1_1") (pintype "passive"))
    )
    (net (code "18") (name "/MCU_ETH_LED3") (class "Default")
      (node (ref "J12") (pin "14") (pinfunction "14_14") (pintype "passive"))
      (node (ref "Q4") (pin "3") (pinfunction "D_3") (pintype "passive"))
      (node (ref "R78") (pin "1") (pinfunction "1_1") (pintype "passive"))
    )
    (net (code "19") (name "/MCU_ETH_LED_1000") (class "Default")
      (node (ref "R73") (pin "2") (pinfunction "2_2") (pintype "passive"))
      (node (ref "R90") (pin "2") (pinfunction "2_2") (pintype "passive"))
      (node (ref "R91") (pin "1") (pinfunction "1_1") (pintype "passive"))
      (node (ref "U22") (pin "46") (pinfunction "LED_1_46") (pintype "passive"))
    )
    (net (code "20") (name "/MCU_ETH_LED_ACTn") (class "Default")
      (node (ref "R451") (pin "2") (pinfunction "2_2") (pintype "passive"))
      (node (ref "R92") (pin "1") (pinfunction "1_1") (pintype "passive"))
      (node (ref "R93") (pin "2") (pinfunction "2_2") (pintype "passive"))
      (node (ref "U22") (pin "45") (pinfunction "LED_2_45") (pintype "passive"))
    )
    (net (code "21") (name "/MCU_MDC_RGMII_1V8") (class "Default")
      (node (ref "R149") (pin "2") (pinfunction "2_2") (pintype "passive"))
      (node (ref "U22") (pin "16") (pinfunction "MDC_16") (pintype "passive"))
      (node (ref "U29") (pin "8") (pinfunction "A1_8") (pintype "bidirectional"))
    )
    (net (code "22") (name "/MCU_MDC_RGMII_3V3") (class "Default")
      (node (ref "R175") (pin "2") (pinfunction "2_2") (pintype "passive"))
      (node (ref "U29") (pin "5") (pinfunction "B1_5") (pintype "bidirectional"))
    )
    (net (code "23") (name "/MCU_MDIO_1V8") (class "Default")
      (node (ref "R156") (pin "2") (pinfunction "2_2") (pintype "passive"))
      (node (ref "U22") (pin "17") (pinfunction "MDIO_17") (pintype "bidirectional"))
      (node (ref "U30") (pin "5") (pinfunction "A1_5") (pintype "bidirectional"))
    )
    (net (code "24") (name "/MCU_MDIO_3V3") (class "Default")
      (node (ref "R174") (pin "2") (pinfunction "2_2") (pintype "passive"))
      (node (ref "U30") (pin "8") (pinfunction "B1_8") (pintype "bidirectional"))
    )
    (net (code "25") (name "/MCU_PORz_OUT") (class "Default")
      (node (ref "R415") (pin "1") (pinfunction "1_1") (pintype "passive"))
      (node (ref "U82") (pin "2") (pinfunction "B_2") (pintype "input"))
    )
    (net (code "26") (name "/MCU_RGMII1_CLKIN") (class "Default")
      (node (ref "U22") (pin "15") (pinfunction "XI_15") (pintype "input"))
    )
    (net (code "27") (name "/MCU_RGMII1_RD0") (class "Default")
      (node (ref "R118") (pin "1") (pinfunction "1_1") (pintype "passive"))
      (node (ref "U34") (pin "L6") (pinfunction "MCU_RGMII1_RD0_L6") (pintype "passive"))
    )
    (net (code "28") (name "/MCU_RGMII1_RD0_R") (class "Default")
      (node (ref "R118") (pin "2") (pinfunction "2_2") (pintype "passive"))
      (node (ref "R119") (pin "2") (pinfunction "2_2") (pintype "passive"))
      (node (ref "R122") (pin "1") (pinfunction "1_1") (pintype "passive"))
      (node (ref "U22") (pin "33") (pinfunction "RX_D0_33") (pintype "passive"))
    )
    (net (code "29") (name "/MCU_RGMII1_RD1") (class "Default")
      (node (ref "R114") (pin "1") (pinfunction "1_1") (pintype "passive"))
      (node (ref "U34") (pin "M6") (pinfunction "MCU_RGMII1_RD1_M6") (pintype "passive"))
    )
    (net (code "30") (name "/MCU_RGMII1_RD1_R") (class "Default")
      (node (ref "R114") (pin "2") (pinfunction "2_2") (pintype "passive"))
      (node (ref "U22") (pin "34") (pinfunction "RX_D1_34") (pintype "passive"))
    )
    (net (code "31") (name "/MCU_RGMII1_RD2") (class "Default")
      (node (ref "R111") (pin "1") (pinfunction "1_1") (pintype "passive"))
      (node (ref "U34") (pin "L5") (pinfunction "MCU_RGMII1_RD2_L5") (pintype "passive"))
    )
    (net (code "32") (name "/MCU_RGMII1_RD2_R") (class "Default")
      (node (ref "R111") (pin "2") (pinfunction "2_2") (pintype "passive"))
      (node (ref "R112") (pin "1") (pinfunction "1_1") (pintype "passive"))
      (node (ref "R115") (pin "2") (pinfunction "2_2") (pintype "passive"))
      (node (ref "U22") (pin "35") (pinfunction "RX_D2_35") (pintype "passive"))
    )
    (net (code "33") (name "/MCU_RGMII1_RD3") (class "Default")
      (node (ref "R102") (pin "1") (pinfunction "1_1") (pintype "passive"))
      (node (ref "U34") (pin "L2") (pinfunction "MCU_RGMII1_RD3_L2") (pintype "passive"))
    )
    (net (code "34") (name "/MCU_RGMII1_RD3_R") (class "Default")
      (node (ref "R102") (pin "2") (pinfunction "2_2") (pintype "passive"))
      (node (ref "U22") (pin "36") (pinfunction "RX_D3_36") (pintype "passive"))
    )
    (net (code "35") (name "/MCU_RGMII1_RXC") (class "Default")
      (node (ref "R121") (pin "1") (pinfunction "1_1") (pintype "passive"))
      (node (ref "U34") (pin "M1") (pinfunction "MCU_RGMII1_RXC_M1") (pintype "passive"))
    )
    (net (code "36") (name "/MCU_RGMII1_RXC_R") (class "Default")
      (node (ref "R121") (pin "2") (pinfunction "2_2") (pintype "passive"))
      (node (ref "U22") (pin "32") (pinfunction "RX_CLK_32") (pintype "passive"))
    )
    (net (code "37") (name "/MCU_RGMII1_RX_CTL") (class "Default")
      (node (ref "R101") (pin "1") (pinfunction "1_1") (pintype "passive"))
      (node (ref "U34") (pin "N5") (pinfunction "MCU_RGMII1_RX_CTL_N5") (pintype "passive"))
    )
    (net (code "38") (name "/MCU_RGMII1_RX_CTL_R") (class "Default")
      (node (ref "R101") (pin "2") (pinfunction "2_2") (pintype "passive"))
      (node (ref "R98") (pin "1") (pinfunction "1_1") (pintype "passive"))
      (node (ref "R99") (pin "1") (pinfunction "1_1") (pintype "passive"))
      (node (ref "U22") (pin "38") (pinfunction "RX_DV/RX_CTRL_38") (pintype "passive"))
    )
    (net (code "39") (name "/MCU_RGMII1_TD0") (class "Default")
      (node (ref "RA7") (pin "4") (pinfunction "4_4") (pintype "passive"))
      (node (ref "U22") (pin "28") (pinfunction "TX_D0_28") (pintype "passive"))
    )
    (net (code "40") (name "/MCU_RGMII1_TD0_R") (class "Default")
      (node (ref "RA7") (pin "5") (pinfunction "5_5") (pintype "passive"))
      (node (ref "U34") (pin "M5") (pinfunction "MCU_RGMII1_TD0_M5") (pintype "passive"))
    )
    (net (code "41") (name "/MCU_RGMII1_TD1") (class "Default")
      (node (ref "RA7") (pin "3") (pinfunction "3_3") (pintype "passive"))
      (node (ref "U22") (pin "27") (pinfunction "TX_D1_27") (pintype "passive"))
    )
    (net (code "42") (name "/MCU_RGMII1_TD1_R") (class "Default")
      (node (ref "RA7") (pin "6") (pinfunction "6_6") (pintype "passive"))
      (node (ref "U34") (pin "M4") (pinfunction "MCU_RGMII1_TD1_M4") (pintype "passive"))
    )
    (net (code "43") (name "/MCU_RGMII1_TD2") (class "Default")
      (node (ref "RA7") (pin "2") (pinfunction "2_2") (pintype "passive"))
      (node (ref "U22") (pin "26") (pinfunction "TX_D2_26") (pintype "passive"))
    )
    (net (code "44") (name "/MCU_RGMII1_TD2_R") (class "Default")
      (node (ref "RA7") (pin "7") (pinfunction "7_7") (pintype "passive"))
      (node (ref "U34") (pin "M3") (pinfunction "MCU_RGMII1_TD2_M3") (pintype "passive"))
    )
    (net (code "45") (name "/MCU_RGMII1_TD3") (class "Default")
      (node (ref "RA7") (pin "1") (pinfunction "1_1") (pintype "passive"))
      (node (ref "U22") (pin "25") (pinfunction "TX_D3_25") (pintype "passive"))
    )
    (net (code "46") (name "/MCU_RGMII1_TD3_R") (class "Default")
      (node (ref "RA7") (pin "8") (pinfunction "8_8") (pintype "passive"))
      (node (ref "U34") (pin "M2") (pinfunction "MCU_RGMII1_TD3_M2") (pintype "passive"))
    )
    (net (code "47") (name "/MCU_RGMII1_TXC") (class "Default")
      (node (ref "R438") (pin "2") (pinfunction "2_2") (pintype "passive"))
      (node (ref "U22") (pin "29") (pinfunction "GTX_CLK_29") (pintype "passive"))
    )
    (net (code "48") (name "/MCU_RGMII1_TXC_R") (class "Default")
      (node (ref "R438") (pin "1") (pinfunction "1_1") (pintype "passive"))
      (node (ref "U34") (pin "N1") (pinfunction "MCU_RGMII1_TXC_N1") (pintype "passive"))
    )
    (net (code "49") (name "/MCU_RGMII1_TX_CTL") (class "Default")
      (node (ref "R439") (pin "2") (pinfunction "2_2") (pintype "passive"))
      (node (ref "U22") (pin "37") (pinfunction "TX_EN/TX_CTRL_37") (pintype "passive"))
    )
    (net (code "50") (name "/MCU_RGMII1_TX_CTL_R") (class "Default")
      (node (ref "R439") (pin "1") (pinfunction "1_1") (pintype "passive"))
      (node (ref "U34") (pin "N4") (pinfunction "MCU_RGMII1_TX_CTL_N4") (pintype "passive"))
    )
    (net (code "51") (name "DGND") (class "Default")
      (node (ref "C101") (pin "2") (pinfunction "2_2") (pintype "passive"))
      (node (ref "C102") (pin "2") (pinfunction "2_2") (pintype "passive"))
      (node (ref "C109") (pin "2") (pinfunction "2_2") (pintype "passive"))
      (node (ref "C110") (pin "2") (pinfunction "2_2") (pintype "passive"))
      (node (ref "C111") (pin "2") (pinfunction "2_2") (pintype "passive"))
      (node (ref "C117") (pin "2") (pinfunction "2_2") (pintype "passive"))
      (node (ref "C120") (pin "2") (pinfunction "2_2") (pintype "passive"))
      (node (ref "C123") (pin "2") (pinfunction "2_2") (pintype "passive"))
      (node (ref "C124") (pin "2") (pinfunction "2_2") (pintype "passive"))
      (node (ref "C134") (pin "2") (pinfunction "2_2") (pintype "passive"))
      (node (ref "C135") (pin "2") (pinfunction "2_2") (pintype "passive"))
      (node (ref "C136") (pin "2") (pinfunction "2_2") (pintype "passive"))
      (node (ref "C138") (pin "2") (pinfunction "2_2") (pintype "passive"))
      (node (ref "C358") (pin "2") (pinfunction "2_2") (pintype "passive"))
      (node (ref "C371") (pin "2") (pinfunction "2_2") (pintype "passive"))
      (node (ref "C372") (pin "2") (pinfunction "2_2") (pintype "passive"))
      (node (ref "C378") (pin "2") (pinfunction "2_2") (pintype "passive"))
      (node (ref "C381") (pin "2") (pinfunction "2_2") (pintype "passive"))
      (node (ref "C388") (pin "2") (pinfunction "2_2") (pintype "passive"))
      (node (ref "C392") (pin "2") (pinfunction "2_2") (pintype "passive"))
      (node (ref "C393") (pin "2") (pinfunction "2_2") (pintype "passive"))
      (node (ref "C394") (pin "2") (pinfunction "2_2") (pintype "passive"))
      (node (ref "C399") (pin "2") (pinfunction "2_2") (pintype "passive"))
      (node (ref "C400") (pin "2") (pinfunction "2_2") (pintype "passive"))
      (node (ref "C403") (pin "2") (pinfunction "2_2") (pintype "passive"))
      (node (ref "C404") (pin "2") (pinfunction "2_2") (pintype "passive"))
      (node (ref "C405") (pin "2") (pinfunction "2_2") (pintype "passive"))
      (node (ref "J12") (pin "1") (pinfunction "CH-GND_1") (pintype "passive"))
      (node (ref "Q3") (pin "2") (pinfunction "S_2") (pintype "passive"))
      (node (ref "Q4") (pin "2") (pinfunction "S_2") (pintype "passive"))
      (node (ref "Q9") (pin "2") (pinfunction "S_2") (pintype "passive"))
      (node (ref "R112") (pin "2") (pinfunction "2_2") (pintype "passive"))
      (node (ref "R122") (pin "2") (pinfunction "2_2") (pintype "passive"))
      (node (ref "R135") (pin "2") (pinfunction "2_2") (pintype "passive"))
      (node (ref "R150") (pin "1") (pinfunction "1_1") (pintype "passive"))
      (node (ref "R164") (pin "1") (pinfunction "1_1") (pintype "passive"))
      (node (ref "R409") (pin "1") (pinfunction "1_1") (pintype "passive"))
      (node (ref "R417") (pin "2") (pinfunction "2_2") (pintype "passive"))
      (node (ref "R456") (pin "2") (pinfunction "2_2") (pintype "passive"))
      (node (ref "R91") (pin "2") (pinfunction "2_2") (pintype "passive"))
      (node (ref "R92") (pin "2") (pinfunction "2_2") (pintype "passive"))
      (node (ref "R95") (pin "2") (pinfunction "2_2") (pintype "passive"))
      (node (ref "R96") (pin "2") (pinfunction "2_2") (pintype "passive"))
      (node (ref "R99") (pin "2") (pinfunction "2_2") (pintype "passive"))
      (node (ref "U22") (pin "49") (pinfunction "GND_49") (pintype "power_in"))
      (node (ref "U29") (pin "3") (pinfunction "GND_3") (pintype "power_in"))
      (node (ref "U30") (pin "2") (pinfunction "GND_2") (pintype "power_in"))
      (node (ref "U82") (pin "3") (pinfunction "GND_3") (pintype "power_in"))
    )
    (net (code "52") (name "MCU_EARTH") (class "Default")
      (node (ref "C405") (pin "1") (pinfunction "1_1") (pintype "passive"))
      (node (ref "J12") (pin "15") (pinfunction "SH1_15") (pintype "passive"))
      (node (ref "J12") (pin "16") (pinfunction "SH2_16") (pintype "passive"))
      (node (ref "R456") (pin "1") (pinfunction "1_1") (pintype "passive"))
    )
    (net (code "53") (name "Net-(J12-Pad11)") (class "Default")
      (node (ref "J12") (pin "11") (pinfunction "11_11") (pintype "passive"))
      (node (ref "R449") (pin "2") (pinfunction "2_2") (pintype "passive"))
    )
    (net (code "54") (name "Net-(J12-VCC)") (class "Default")
      (node (ref "FL11") (pin "2") (pinfunction "2_2") (pintype "passive"))
      (node (ref "J12") (pin "2") (pinfunction "VCC_2") (pintype "passive"))
    )
    (net (code "55") (name "Net-(Q3-G)") (class "Default")
      (node (ref "Q3") (pin "1") (pinfunction "G_1") (pintype "passive"))
      (node (ref "R73") (pin "1") (pinfunction "1_1") (pintype "passive"))
    )
    (net (code "56") (name "Net-(Q4-G)") (class "Default")
      (node (ref "Q4") (pin "1") (pinfunction "G_1") (pintype "passive"))
      (node (ref "R72") (pin "1") (pinfunction "1_1") (pintype "passive"))
    )
    (net (code "57") (name "Net-(Q9-G)") (class "Default")
      (node (ref "Q9") (pin "1") (pinfunction "G_1") (pintype "passive"))
      (node (ref "R451") (pin "1") (pinfunction "1_1") (pintype "passive"))
    )
    (net (code "58") (name "Net-(TP12-TP)") (class "Default")
      (node (ref "TP12") (pin "1") (pinfunction "TP_1") (pintype "passive"))
      (node (ref "U22") (pin "13") (pinfunction "VDDA1P8_13") (pintype "power_in"))
      (node (ref "U22") (pin "48") (pinfunction "VDDA1P8_48") (pintype "power_in"))
    )
    (net (code "59") (name "Net-(U29-DIR1)") (class "Default")
      (node (ref "R150") (pin "2") (pinfunction "2_2") (pintype "passive"))
      (node (ref "U29") (pin "1") (pinfunction "DIR2_1") (pintype "input"))
      (node (ref "U29") (pin "10") (pinfunction "DIR1_10") (pintype "input"))
    )
    (net (code "60") (name "Net-(U29-~{OE})") (class "Default")
      (node (ref "R164") (pin "2") (pinfunction "2_2") (pintype "passive"))
      (node (ref "U29") (pin "2") (pinfunction "~{OE}_2") (pintype "input"))
    )
    (net (code "61") (name "Net-(U30-OE)") (class "Default")
      (node (ref "R160") (pin "2") (pinfunction "2_2") (pintype "passive"))
      (node (ref "U30") (pin "6") (pinfunction "OE_6") (pintype "input"))
    )
    (net (code "62") (name "VCC1V8") (class "Default")
      (node (ref "C102") (pin "1") (pinfunction "1_1") (pintype "passive"))
      (node (ref "C120") (pin "1") (pinfunction "1_1") (pintype "passive"))
      (node (ref "C123") (pin "1") (pinfunction "1_1") (pintype "passive"))
      (node (ref "C134") (pin "1") (pinfunction "1_1") (pintype "passive"))
      (node (ref "C135") (pin "1") (pinfunction "1_1") (pintype "passive"))
      (node (ref "C358") (pin "1") (pinfunction "1_1") (pintype "passive"))
      (node (ref "C371") (pin "1") (pinfunction "1_1") (pintype "passive"))
      (node (ref "C394") (pin "1") (pinfunction "1_1") (pintype "passive"))
      (node (ref "C400") (pin "1") (pinfunction "1_1") (pintype "passive"))
      (node (ref "C404") (pin "1") (pinfunction "1_1") (pintype "passive"))
      (node (ref "FL11") (pin "1") (pinfunction "1_1") (pintype "passive"))
      (node (ref "R100") (pin "2") (pinfunction "2_2") (pintype "passive"))
      (node (ref "R115") (pin "1") (pinfunction "1_1") (pintype "passive"))
      (node (ref "R119") (pin "1") (pinfunction "1_1") (pintype "passive"))
      (node (ref "R149") (pin "1") (pinfunction "1_1") (pintype "passive"))
      (node (ref "R156") (pin "1") (pinfunction "1_1") (pintype "passive"))
      (node (ref "R160") (pin "1") (pinfunction "1_1") (pintype "passive"))
      (node (ref "R90") (pin "1") (pinfunction "1_1") (pintype "passive"))
      (node (ref "R93") (pin "1") (pinfunction "1_1") (pintype "passive"))
      (node (ref "R94") (pin "1") (pinfunction "1_1") (pintype "passive"))
      (node (ref "R97") (pin "1") (pinfunction "1_1") (pintype "passive"))
      (node (ref "R98") (pin "2") (pinfunction "2_2") (pintype "passive"))
      (node (ref "U22") (pin "19") (pinfunction "VDDIO_19") (pintype "power_in"))
      (node (ref "U22") (pin "30") (pinfunction "VDDIO_30") (pintype "power_in"))
      (node (ref "U22") (pin "41") (pinfunction "VDDIO_41") (pintype "power_in"))
      (node (ref "U29") (pin "7") (pinfunction "VCCA_7") (pintype "power_in"))
      (node (ref "U30") (pin "3") (pinfunction "VCCA_3") (pintype "power_in"))
      (node (ref "U82") (pin "5") (pinfunction "VCC_5") (pintype "power_in"))
    )
    (net (code "63") (name "VCC3V3_IO") (class "Default")
      (node (ref "C136") (pin "1") (pinfunction "1_1") (pintype "passive"))
      (node (ref "C138") (pin "1") (pinfunction "1_1") (pintype "passive"))
      (node (ref "R174") (pin "1") (pinfunction "1_1") (pintype "passive"))
      (node (ref "R175") (pin "1") (pinfunction "1_1") (pintype "passive"))
      (node (ref "R412") (pin "2") (pinfunction "2_2") (pintype "passive"))
      (node (ref "R415") (pin "2") (pinfunction "2_2") (pintype "passive"))
      (node (ref "R449") (pin "1") (pinfunction "1_1") (pintype "passive"))
      (node (ref "R78") (pin "2") (pinfunction "2_2") (pintype "passive"))
      (node (ref "R79") (pin "2") (pinfunction "2_2") (pintype "passive"))
      (node (ref "U29") (pin "6") (pinfunction "VCCB_6") (pintype "power_in"))
      (node (ref "U30") (pin "7") (pinfunction "VCCB_7") (pintype "power_in"))
    )
    (net (code "64") (name "VDD_1V0") (class "Default")
      (node (ref "C101") (pin "1") (pinfunction "1_1") (pintype "passive"))
      (node (ref "C110") (pin "1") (pinfunction "1_1") (pintype "passive"))
      (node (ref "C111") (pin "1") (pinfunction "1_1") (pintype "passive"))
      (node (ref "C124") (pin "1") (pinfunction "1_1") (pintype "passive"))
      (node (ref "C372") (pin "1") (pinfunction "1_1") (pintype "passive"))
      (node (ref "C388") (pin "1") (pinfunction "1_1") (pintype "passive"))
      (node (ref "C392") (pin "1") (pinfunction "1_1") (pintype "passive"))
      (node (ref "C399") (pin "1") (pinfunction "1_1") (pintype "passive"))
      (node (ref "C403") (pin "1") (pinfunction "1_1") (pintype "passive"))
      (node (ref "U22") (pin "24") (pinfunction "VDD1P0_24") (pintype "power_in"))
      (node (ref "U22") (pin "31") (pinfunction "VDD1P0_31") (pintype "power_in"))
      (node (ref "U22") (pin "42") (pinfunction "VDD1P0_42") (pintype "power_in"))
      (node (ref "U22") (pin "6") (pinfunction "VDD1P0_6") (pintype "power_in"))
    )
    (net (code "65") (name "VDD_2V5") (class "Default")
      (node (ref "C109") (pin "1") (pinfunction "1_1") (pintype "passive"))
      (node (ref "C117") (pin "1") (pinfunction "1_1") (pintype "passive"))
      (node (ref "C378") (pin "1") (pinfunction "1_1") (pintype "passive"))
      (node (ref "C381") (pin "1") (pinfunction "1_1") (pintype "passive"))
      (node (ref "C393") (pin "1") (pinfunction "1_1") (pintype "passive"))
      (node (ref "U22") (pin "3") (pinfunction "VDDA2P5_3") (pintype "power_in"))
      (node (ref "U22") (pin "9") (pinfunction "VDDA2P5_9") (pintype "power_in"))
    )
    (net (code "66") (name "unconnected-(U22-JTAG_CLK-Pad20)") (class "Default")
      (node (ref "U22") (pin "20") (pinfunction "JTAG_CLK_20") (pintype "input+no_connect"))
    )
    (net (code "67") (name "unconnected-(U22-JTAG_TDI-Pad23)") (class "Default")
      (node (ref "U22") (pin "23") (pinfunction "JTAG_TDI_23") (pintype "input+no_connect"))
    )
    (net (code "68") (name "unconnected-(U22-JTAG_TDO-Pad21)") (class "Default")
      (node (ref "U22") (pin "21") (pinfunction "JTAG_TDO_21") (pintype "output+no_connect"))
    )
    (net (code "69") (name "unconnected-(U22-JTAG_TMS-Pad22)") (class "Default")
      (node (ref "U22") (pin "22") (pinfunction "JTAG_TMS_22") (pintype "bidirectional+no_connect"))
    )
    (net (code "70") (name "unconnected-(U22-LED_0-Pad47)") (class "Default")
      (node (ref "U22") (pin "47") (pinfunction "LED_0_47") (pintype "passive+no_connect"))
    )
    (net (code "71") (name "unconnected-(U22-XO-Pad14)") (class "Default")
      (node (ref "U22") (pin "14") (pinfunction "XO_14") (pintype "output+no_connect"))
    )
    (net (code "72") (name "unconnected-(U29-A2-Pad9)") (class "Default")
      (node (ref "U29") (pin "9") (pinfunction "A2_9") (pintype "bidirectional+no_connect"))
    )
    (net (code "73") (name "unconnected-(U29-B2-Pad4)") (class "Default")
      (node (ref "U29") (pin "4") (pinfunction "B2_4") (pintype "bidirectional+no_connect"))
    )
    (net (code "74") (name "unconnected-(U30-A2-Pad4)") (class "Default")
      (node (ref "U30") (pin "4") (pinfunction "A2_4") (pintype "bidirectional+no_connect"))
    )
    (net (code "75") (name "unconnected-(U30-B2-Pad1)") (class "Default")
      (node (ref "U30") (pin "1") (pinfunction "B2_1") (pintype "bidirectional+no_connect"))
    )
  )
)
